# Ethernet_Connector.net
KiCad netlist of a schematic drawn in Altium Designer
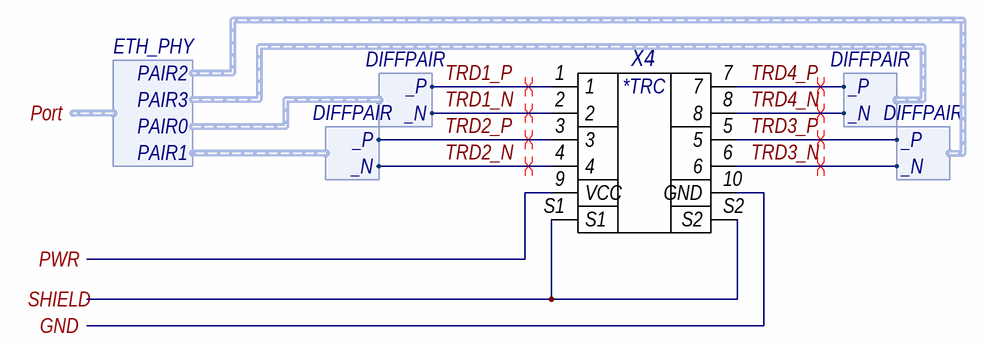
[diagram p0: Ethernet Connector.SchDoc]

(export (version "E")
  (design (tool "Eeschema 10.0.6"))
  (components
    (comp (ref "X4")
      (value "7499111001A")
      (footprint "WE-7499111001A_V")
      (description "RJ45 LAN Transformer, Modular JACK, 0 to 70 degC, 10-Pin THD, RoHS, Tube")
      (libsource (lib "MiniPC DB") (part "NABOR_RJ45_1"))
    )
  )
  (nets
    (net (code "3") (name "/GND") (class "Default")
      (node (ref "X4") (pin "10") (pinfunction "GND_10") (pintype "passive"))
    )
    (net (code "4") (name "/PWR") (class "Default")
      (node (ref "X4") (pin "9") (pinfunction "VCC_9") (pintype "passive"))
    )
    (net (code "6") (name "/SHIELD") (class "Default")
      (node (ref "X4") (pin "S1") (pinfunction "S1_S1") (pintype "passive"))
      (node (ref "X4") (pin "S2") (pinfunction "S2_S2") (pintype "passive"))
    )
    (net (code "7") (name "/TRD1_N") (class "Default")
      (node (ref "X4") (pin "2") (pinfunction "2_2") (pintype "passive"))
    )
    (net (code "8") (name "/TRD1_P") (class "Default")
      (node (ref "X4") (pin "1") (pinfunction "1_1") (pintype "passive"))
    )
    (net (code "9") (name "/TRD2_N") (class "Default")
      (node (ref "X4") (pin "4") (pinfunction "4_4") (pintype "passive"))
    )
    (net (code "10") (name "/TRD2_P") (class "Default")
      (node (ref "X4") (pin "3") (pinfunction "3_3") (pintype "passive"))
    )
    (net (code "11") (name "/TRD3_N") (class "Default")
      (node (ref "X4") (pin "6") (pinfunction "6_6") (pintype "passive"))
    )
    (net (code "12") (name "/TRD3_P") (class "Default")
      (node (ref "X4") (pin "5") (pinfunction "5_5") (pintype "passive"))
    )
    (net (code "13") (name "/TRD4_N") (class "Default")
      (node (ref "X4") (pin "8") (pinfunction "8_8") (pintype "passive"))
    )
    (net (code "14") (name "/TRD4_P") (class "Default")
      (node (ref "X4") (pin "7") (pinfunction "7_7") (pintype "passive"))
    )
  )
)
